# 105358-3SC001-03_PWR_MGMT.net
KiCad netlist of a schematic drawn in Altium Designer
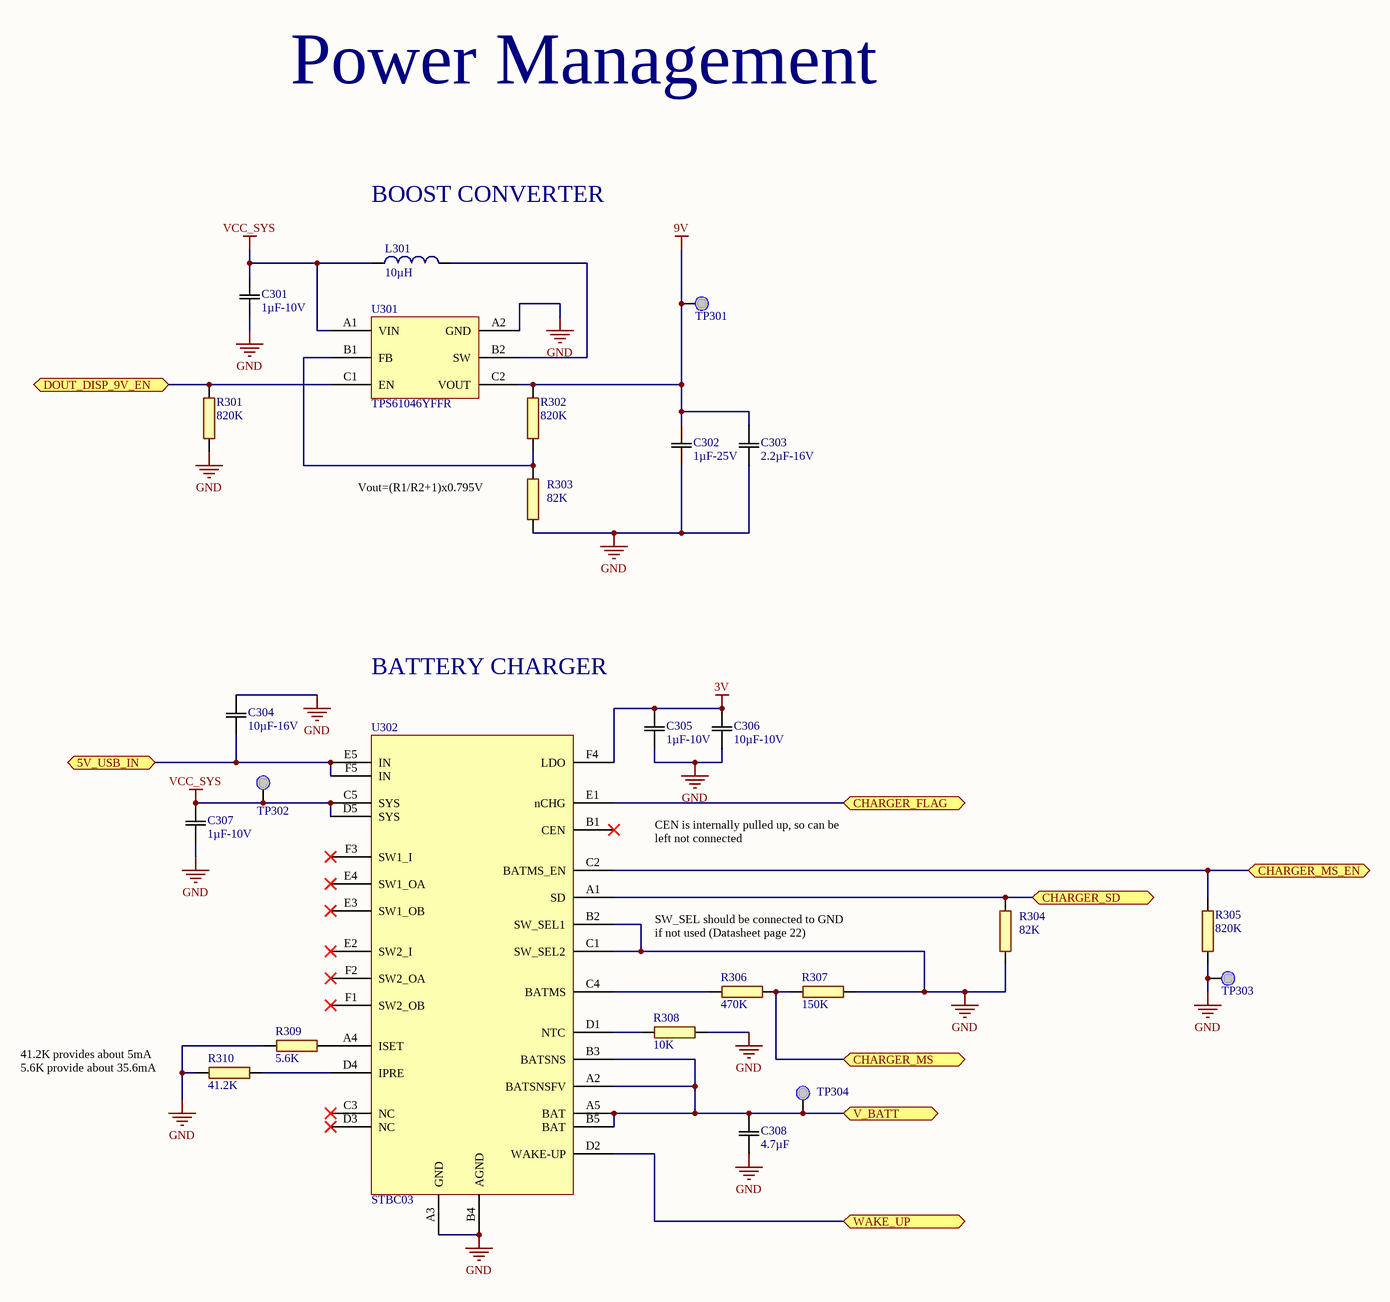
[diagram p0: 105358-3SC001-03_PWR_MGMT.SchDoc]

(export (version "E")
  (design (tool "Eeschema 10.0.6"))
  (components
    (comp (ref "C301")
      (value "1µF-10V")
      (footprint "0402C_HIGH_DENSITY")
      (description "1µF ±10% 10V X5R Ceramic Capacitor 0402")
      (fields
        (field (name "MANUFACTURER PART NUMBER") "CC0402KRX5R6BB105")
        (field (name "MANUFACTURER") "Yageo")
      )
      (libsource (lib "ConnectMedical") (part "0402C-1uF-10V"))
    )
    (comp (ref "C302")
      (value "1µF-25V")
      (footprint "0402C_HIGH_DENSITY")
      (description "CAP CER 1UF 25V X5R 0402")
      (fields
        (field (name "MANUFACTURER PART NUMBER") "TMK105BJ105KV-F")
        (field (name "MANUFACTURER") "Taiyo Yuden")
      )
      (libsource (lib "ConnectMedical") (part "0402C-1uF-25V"))
    )
    (comp (ref "C303")
      (value "2.2µF-16V")
      (footprint "0402C_HIGH_DENSITY")
      (description "CAP CER 2.2UF 16V X5R 0402")
      (fields
        (field (name "MANUFACTURER PART NUMBER") "GRM155R61C225KE44D")
        (field (name "MANUFACTURER") "Murata Electronics North America")
      )
      (libsource (lib "ConnectMedical") (part "0402C-2,2uF-16V"))
    )
    (comp (ref "C304")
      (value "10µF-16V")
      (footprint "0603C_HIGH_DENSITY")
      (description "10µF ±10% 16V X5R Ceramic Capacitor 0603")
      (fields
        (field (name "MANUFACTURER PART NUMBER") "GRT188R61C106KE13D")
        (field (name "MANUFACTURER") "Murata Electronics North America")
      )
      (libsource (lib "ConnectMedical") (part "0603C-10uF-16V"))
    )
    (comp (ref "C305")
      (value "1µF-10V")
      (footprint "0402C_HIGH_DENSITY")
      (description "1µF ±10% 10V X5R Ceramic Capacitor 0402")
      (fields
        (field (name "MANUFACTURER PART NUMBER") "CC0402KRX5R6BB105")
        (field (name "MANUFACTURER") "Yageo")
      )
      (libsource (lib "ConnectMedical") (part "0402C-1uF-10V"))
    )
    (comp (ref "C306")
      (value "10µF-10V")
      (footprint "0603C-GENERIC")
      (description "10µF ±10% 10V X5R Ceramic Capacitor 0603")
      (fields
        (field (name "MANUFACTURER PART NUMBER") "GRM188R61A106KE69D")
        (field (name "MANUFACTURER") "Murata Electronics North America")
      )
      (libsource (lib "ConnectMedical") (part "0603C-10uF-10V"))
    )
    (comp (ref "C307")
      (value "1µF-10V")
      (footprint "0402C_HIGH_DENSITY")
      (description "1µF ±10% 10V X5R Ceramic Capacitor 0402")
      (fields
        (field (name "MANUFACTURER PART NUMBER") "CC0402KRX5R6BB105")
        (field (name "MANUFACTURER") "Yageo")
      )
      (libsource (lib "ConnectMedical") (part "0402C-1uF-10V"))
    )
    (comp (ref "C308")
      (value "4.7µF")
      (footprint "0402C_HIGH_DENSITY")
      (description "4.7µF ±10% 6.3V X5R Ceramic Capacitor 0402")
      (fields
        (field (name "MANUFACTURER PART NUMBER") "C1005X5R0J475K050BC")
        (field (name "MANUFACTURER") "TDK Corporation")
      )
      (libsource (lib "ConnectMedical") (part "0402C-4.7uF-6.3V"))
    )
    (comp (ref "L301")
      (value "10µH")
      (footprint "0805L_HIGH_DENSITY")
      (description "FIXED IND 10UH 500MA 300 MOHM")
      (fields
        (field (name "DIGI-KEY PART NUMBER") "445-6762-1-ND")
        (field (name "MANUFACTURER") "TDK Corporation")
      )
      (libsource (lib "ConnectMedical") (part "0805L-10uH-0.39Ohm"))
    )
    (comp (ref "R301")
      (value "820K")
      (footprint "0402R-GENERIC")
      (description "RES SMD 820kOHM 1% 1/16W 0402")
      (fields (field (name "DIGI-KEY PART NUMBER") "YAG3240CT-ND") (field (name "MANUFACTURER") "Yageo"))
      (libsource (lib "ConnectMedical") (part "0402R-820k OHM-1%-0.063W"))
    )
    (comp (ref "R302")
      (value "820K")
      (footprint "0402R-GENERIC")
      (description "RES SMD 820kOHM 1% 1/16W 0402")
      (fields (field (name "DIGI-KEY PART NUMBER") "YAG3240CT-ND") (field (name "MANUFACTURER") "Yageo"))
      (libsource (lib "ConnectMedical") (part "0402R-820k OHM-1%-0.063W"))
    )
    (comp (ref "R303")
      (value "82K")
      (footprint "0402R-GENERIC")
      (description "RES SMD 82kOHM 1% 1/16W 0402")
      (fields (field (name "DIGI-KEY PART NUMBER") "311-82.0KLRCT-ND") (field (name "MANUFACTURER") "Yageo"))
      (libsource (lib "ConnectMedical") (part "0402R-82k OHM-1%-0.063W"))
    )
    (comp (ref "R304")
      (value "82K")
      (footprint "0402R-GENERIC")
      (description "RES SMD 82kOHM 1% 1/16W 0402")
      (fields (field (name "DIGI-KEY PART NUMBER") "311-82.0KLRCT-ND") (field (name "MANUFACTURER") "Yageo"))
      (libsource (lib "ConnectMedical") (part "0402R-82k OHM-1%-0.063W"))
    )
    (comp (ref "R305")
      (value "820K")
      (footprint "0402R-GENERIC")
      (description "RES SMD 820kOHM 1% 1/16W 0402")
      (fields (field (name "DIGI-KEY PART NUMBER") "YAG3240CT-ND") (field (name "MANUFACTURER") "Yageo"))
      (libsource (lib "ConnectMedical") (part "0402R-820k OHM-1%-0.063W"))
    )
    (comp (ref "R306")
      (value "470K")
      (footprint "0402R-GENERIC")
      (description "RES SMD 470K OHM 1% 1/16W 0402")
      (fields (field (name "TOLERANCE") "1%") (field (name "POWER") "0.063W"))
      (libsource (lib "ConnectMedical") (part "0402R-470K OHM-1%-0.063W"))
    )
    (comp (ref "R307")
      (value "150K")
      (footprint "0402R-GENERIC")
      (description "RES SMD 150kOHM 5% 1/16W 0402")
      (fields (field (name "DIGI-KEY PART NUMBER") "311-150KJRCT-ND") (field (name "MANUFACTURER") "Yageo"))
      (libsource (lib "ConnectMedical") (part "0402R-150k OHM-5%-0.063W"))
    )
    (comp (ref "R308")
      (value "10K")
      (footprint "0402R-GENERIC")
      (description "RES SMD 10kOHM 1% 1/16W 0402")
      (fields (field (name "DIGI-KEY PART NUMBER") "311-10.0KLRCT-ND") (field (name "MANUFACTURER") "Yageo"))
      (libsource (lib "ConnectMedical") (part "0402R-10k OHM-1%-0.063W"))
    )
    (comp (ref "R309")
      (value "5.6K")
      (footprint "0402R-GENERIC")
      (description "RES SMD 5.6kOHM 5% 1/16W 0402")
      (fields (field (name "DIGI-KEY PART NUMBER") "311-5.6KJRCT-ND") (field (name "MANUFACTURER") "Yageo"))
      (libsource (lib "ConnectMedical") (part "0402R-5.6k OHM-5%-0.063W"))
    )
    (comp (ref "R310")
      (value "41.2K")
      (footprint "0402R-GENERIC")
      (description "RES SMD 41.2kOHM 1% 1/16W 0402")
      (fields (field (name "DIGI-KEY PART NUMBER") "YAG3155CT-ND") (field (name "MANUFACTURER") "Yageo"))
      (libsource (lib "ConnectMedical") (part "0402R-41.2k OHM-1%-0.063W"))
    )
    (comp (ref "TP301")
      (value "TEST POINT")
      (footprint "PAD TEST POINT")
      (description "Testing Poiny")
      (libsource (lib "ConnectMedical") (part "TEST POINT"))
    )
    (comp (ref "TP302")
      (value "TEST POINT")
      (footprint "PAD TEST POINT")
      (description "Testing Poiny")
      (libsource (lib "ConnectMedical") (part "TEST POINT"))
    )
    (comp (ref "TP303")
      (value "TEST POINT")
      (footprint "PAD TEST POINT")
      (description "Testing Poiny")
      (libsource (lib "ConnectMedical") (part "TEST POINT"))
    )
    (comp (ref "TP304")
      (value "TEST POINT")
      (footprint "PAD TEST POINT")
      (description "Testing Poiny")
      (libsource (lib "ConnectMedical") (part "TEST POINT"))
    )
    (comp (ref "U301")
      (value "TPS61046YFFR")
      (footprint "TPS61046YFFR")
      (description "Boost converter 28V")
      (fields
        (field (name "MANUFACTURER") "Texas Instruments")
        (field (name "DIGI-KEY PART NUMBER") "296-44337-1-ND")
      )
      (libsource (lib "ConnectMedical") (part "TPS61046YFFR"))
    )
    (comp (ref "U302")
      (value "STBC03")
      (footprint "STBC03")
      (description "Li-Ion linear battery charger")
      (fields
        (field (name "MANUFACTURER PART NUMBER") "STBC03JR")
        (field (name "MANUFACTURER") "STMicroelectronics")
      )
      (libsource (lib "ConnectMedical") (part "STBC03"))
    )
  )
  (nets
    (net (code "1") (name "/5V_USB_IN") (class "Default")
      (node (ref "C304") (pin "1") (pinfunction "1_1") (pintype "passive"))
      (node (ref "U302") (pin "E5") (pinfunction "IN_E5") (pintype "passive"))
      (node (ref "U302") (pin "F5") (pinfunction "IN_F5") (pintype "passive"))
    )
    (net (code "2") (name "/CHARGER_FLAG") (class "Default")
      (node (ref "U302") (pin "E1") (pinfunction "nCHG_E1") (pintype "passive"))
    )
    (net (code "3") (name "/CHARGER_MS") (class "Default")
      (node (ref "R306") (pin "2") (pintype "passive"))
      (node (ref "R307") (pin "1") (pintype "passive"))
    )
    (net (code "4") (name "/CHARGER_MS_EN") (class "Default")
      (node (ref "R305") (pin "1") (pintype "passive"))
      (node (ref "U302") (pin "C2") (pinfunction "BATMS_EN_C2") (pintype "passive"))
    )
    (net (code "5") (name "/CHARGER_SD") (class "Default")
      (node (ref "R304") (pin "1") (pintype "passive"))
      (node (ref "U302") (pin "A1") (pinfunction "SD_A1") (pintype "passive"))
    )
    (net (code "6") (name "/DOUT_DISP_9V_EN") (class "Default")
      (node (ref "R301") (pin "1") (pintype "passive"))
      (node (ref "U301") (pin "C1") (pinfunction "EN_C1") (pintype "passive"))
    )
    (net (code "7") (name "/V_BATT") (class "Default")
      (node (ref "C308") (pin "2") (pinfunction "2_2") (pintype "passive"))
      (node (ref "TP304") (pin "1") (pinfunction "Test_Point_1") (pintype "passive"))
      (node (ref "U302") (pin "A2") (pinfunction "BATSNSFV_A2") (pintype "passive"))
      (node (ref "U302") (pin "A5") (pinfunction "BAT_A5") (pintype "passive"))
      (node (ref "U302") (pin "B3") (pinfunction "BATSNS_B3") (pintype "passive"))
      (node (ref "U302") (pin "B5") (pinfunction "BAT_B5") (pintype "passive"))
    )
    (net (code "8") (name "/WAKE_UP") (class "Default")
      (node (ref "U302") (pin "D2") (pinfunction "WAKE-UP_D2") (pintype "passive"))
    )
    (net (code "9") (name "3V") (class "Default")
      (node (ref "C305") (pin "2") (pinfunction "2_2") (pintype "passive"))
      (node (ref "C306") (pin "2") (pinfunction "2_2") (pintype "passive"))
      (node (ref "U302") (pin "F4") (pinfunction "LDO_F4") (pintype "passive"))
    )
    (net (code "10") (name "9V") (class "Default")
      (node (ref "C302") (pin "2") (pinfunction "2_2") (pintype "passive"))
      (node (ref "C303") (pin "2") (pinfunction "2_2") (pintype "passive"))
      (node (ref "R302") (pin "1") (pintype "passive"))
      (node (ref "TP301") (pin "1") (pinfunction "Test_Point_1") (pintype "passive"))
      (node (ref "U301") (pin "C2") (pinfunction "VOUT_C2") (pintype "passive"))
    )
    (net (code "11") (name "GND") (class "Default")
      (node (ref "C301") (pin "1") (pinfunction "1_1") (pintype "passive"))
      (node (ref "C302") (pin "1") (pinfunction "1_1") (pintype "passive"))
      (node (ref "C303") (pin "1") (pinfunction "1_1") (pintype "passive"))
      (node (ref "C304") (pin "2") (pinfunction "2_2") (pintype "passive"))
      (node (ref "C305") (pin "1") (pinfunction "1_1") (pintype "passive"))
      (node (ref "C306") (pin "1") (pinfunction "1_1") (pintype "passive"))
      (node (ref "C307") (pin "1") (pinfunction "1_1") (pintype "passive"))
      (node (ref "C308") (pin "1") (pinfunction "1_1") (pintype "passive"))
      (node (ref "R301") (pin "2") (pintype "passive"))
      (node (ref "R303") (pin "2") (pintype "passive"))
      (node (ref "R304") (pin "2") (pintype "passive"))
      (node (ref "R305") (pin "2") (pintype "passive"))
      (node (ref "R307") (pin "2") (pintype "passive"))
      (node (ref "R308") (pin "2") (pintype "passive"))
      (node (ref "R309") (pin "1") (pintype "passive"))
      (node (ref "R310") (pin "1") (pintype "passive"))
      (node (ref "TP303") (pin "1") (pinfunction "Test_Point_1") (pintype "passive"))
      (node (ref "U301") (pin "A2") (pinfunction "GND_A2") (pintype "passive"))
      (node (ref "U302") (pin "A3") (pinfunction "GND_A3") (pintype "passive"))
      (node (ref "U302") (pin "B2") (pinfunction "SW_SEL1_B2") (pintype "passive"))
      (node (ref "U302") (pin "B4") (pinfunction "AGND_B4") (pintype "passive"))
      (node (ref "U302") (pin "C1") (pinfunction "SW_SEL2_C1") (pintype "passive"))
    )
    (net (code "12") (name "Net-(U301-FB)") (class "Default")
      (node (ref "R302") (pin "2") (pintype "passive"))
      (node (ref "R303") (pin "1") (pintype "passive"))
      (node (ref "U301") (pin "B1") (pinfunction "FB_B1") (pintype "passive"))
    )
    (net (code "13") (name "Net-(U301-SW)") (class "Default")
      (node (ref "L301") (pin "2") (pinfunction "2_2") (pintype "passive"))
      (node (ref "U301") (pin "B2") (pinfunction "SW_B2") (pintype "passive"))
    )
    (net (code "14") (name "Net-(U302-BATMS)") (class "Default")
      (node (ref "R306") (pin "1") (pintype "passive"))
      (node (ref "U302") (pin "C4") (pinfunction "BATMS_C4") (pintype "passive"))
    )
    (net (code "15") (name "Net-(U302-IPRE)") (class "Default")
      (node (ref "R310") (pin "2") (pintype "passive"))
      (node (ref "U302") (pin "D4") (pinfunction "IPRE_D4") (pintype "passive"))
    )
    (net (code "16") (name "Net-(U302-ISET)") (class "Default")
      (node (ref "R309") (pin "2") (pintype "passive"))
      (node (ref "U302") (pin "A4") (pinfunction "ISET_A4") (pintype "passive"))
    )
    (net (code "17") (name "Net-(U302-NTC)") (class "Default")
      (node (ref "R308") (pin "1") (pintype "passive"))
      (node (ref "U302") (pin "D1") (pinfunction "NTC_D1") (pintype "passive"))
    )
    (net (code "18") (name "VCC_SYS") (class "Default")
      (node (ref "C301") (pin "2") (pinfunction "2_2") (pintype "passive"))
      (node (ref "C307") (pin "2") (pinfunction "2_2") (pintype "passive"))
      (node (ref "L301") (pin "1") (pinfunction "1_1") (pintype "passive"))
      (node (ref "TP302") (pin "1") (pinfunction "Test_Point_1") (pintype "passive"))
      (node (ref "U301") (pin "A1") (pinfunction "VIN_A1") (pintype "passive"))
      (node (ref "U302") (pin "C5") (pinfunction "SYS_C5") (pintype "passive"))
      (node (ref "U302") (pin "D5") (pinfunction "SYS_D5") (pintype "passive"))
    )
    (net (code "19") (name "unconnected-(U302-CEN-PadB1)") (class "Default")
      (node (ref "U302") (pin "B1") (pinfunction "CEN_B1") (pintype "passive+no_connect"))
    )
    (net (code "20") (name "unconnected-(U302-NC-PadC3)") (class "Default")
      (node (ref "U302") (pin "C3") (pinfunction "NC_C3") (pintype "passive+no_connect"))
    )
    (net (code "21") (name "unconnected-(U302-NC-PadD3)") (class "Default")
      (node (ref "U302") (pin "D3") (pinfunction "NC_D3") (pintype "passive+no_connect"))
    )
    (net (code "22") (name "unconnected-(U302-SW1_I-PadF3)") (class "Default")
      (node (ref "U302") (pin "F3") (pinfunction "SW1_I_F3") (pintype "passive+no_connect"))
    )
    (net (code "23") (name "unconnected-(U302-SW1_OA-PadE4)") (class "Default")
      (node (ref "U302") (pin "E4") (pinfunction "SW1_OA_E4") (pintype "passive+no_connect"))
    )
    (net (code "24") (name "unconnected-(U302-SW1_OB-PadE3)") (class "Default")
      (node (ref "U302") (pin "E3") (pinfunction "SW1_OB_E3") (pintype "passive+no_connect"))
    )
    (net (code "25") (name "unconnected-(U302-SW2_I-PadE2)") (class "Default")
      (node (ref "U302") (pin "E2") (pinfunction "SW2_I_E2") (pintype "passive+no_connect"))
    )
    (net (code "26") (name "unconnected-(U302-SW2_OA-PadF2)") (class "Default")
      (node (ref "U302") (pin "F2") (pinfunction "SW2_OA_F2") (pintype "passive+no_connect"))
    )
    (net (code "27") (name "unconnected-(U302-SW2_OB-PadF1)") (class "Default")
      (node (ref "U302") (pin "F1") (pinfunction "SW2_OB_F1") (pintype "passive+no_connect"))
    )
  )
)
